# ST_LINK_V2-1.net
KiCad netlist of a schematic drawn in Altium Designer
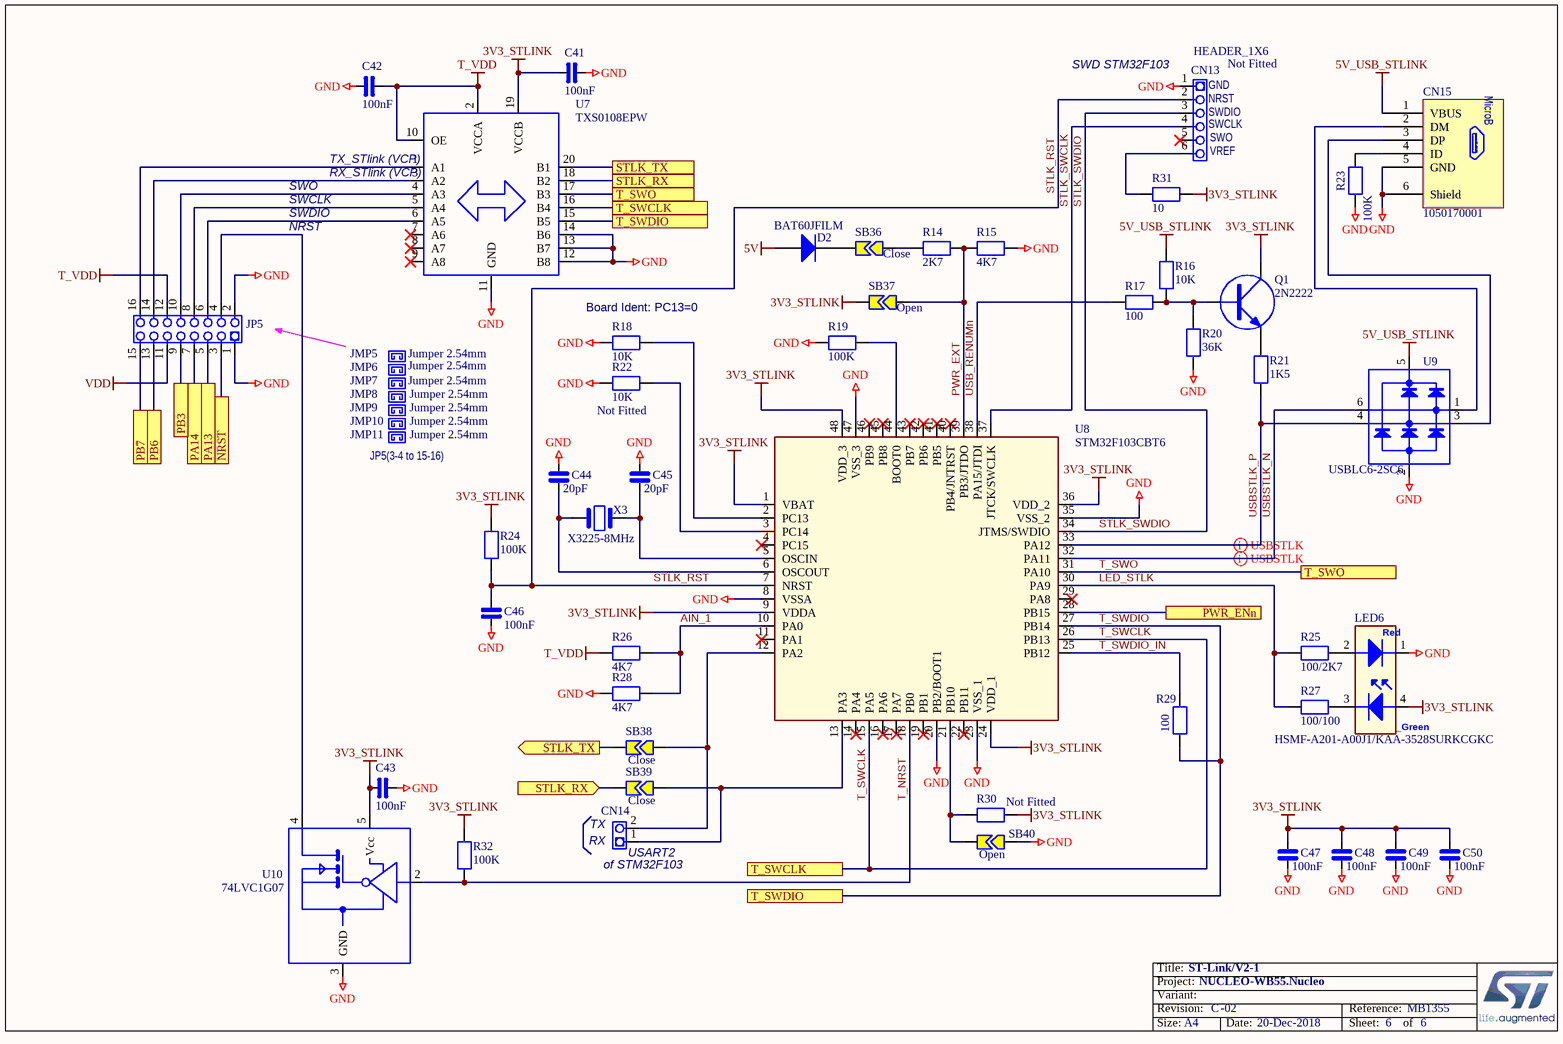
[diagram p0: ST_LINK_V2-1.SCHDOC]

(export (version "E")
  (design (tool "Eeschema 10.0.6"))
  (components
    (comp (ref "C41")
      (value "100nF")
      (footprint "0402_CAP_NPOL")
      (description "Capacitor_not polarized")
      (libsource (lib "ST_Lib3D") (part "CAP_NPOL"))
    )
    (comp (ref "C42")
      (value "100nF")
      (footprint "0402_CAP_NPOL")
      (description "Capacitor_not polarized")
      (libsource (lib "ST_Lib3D") (part "CAP_NPOL"))
    )
    (comp (ref "C43")
      (value "100nF")
      (footprint "0402_CAP_NPOL")
      (description "Capacitor_not polarized")
      (libsource (lib "ST_Lib3D") (part "CAP_NPOL"))
    )
    (comp (ref "C44")
      (value "20pF")
      (footprint "0402_CAP_NPOL")
      (description "Capacitor_not polarized")
      (libsource (lib "ST_Lib3D") (part "CAP_NPOL"))
    )
    (comp (ref "C45")
      (value "20pF")
      (footprint "0402_CAP_NPOL")
      (description "Capacitor_not polarized")
      (libsource (lib "ST_Lib3D") (part "CAP_NPOL"))
    )
    (comp (ref "C46")
      (value "100nF")
      (footprint "0402_CAP_NPOL")
      (description "Capacitor_not polarized")
      (libsource (lib "ST_Lib3D") (part "CAP_NPOL"))
    )
    (comp (ref "C47")
      (value "100nF")
      (footprint "0402_CAP_NPOL")
      (description "Capacitor_not polarized")
      (libsource (lib "ST_Lib3D") (part "CAP_NPOL"))
    )
    (comp (ref "C48")
      (value "100nF")
      (footprint "0402_CAP_NPOL")
      (description "Capacitor_not polarized")
      (libsource (lib "ST_Lib3D") (part "CAP_NPOL"))
    )
    (comp (ref "C49")
      (value "100nF")
      (footprint "0402_CAP_NPOL")
      (description "Capacitor_not polarized")
      (libsource (lib "ST_Lib3D") (part "CAP_NPOL"))
    )
    (comp (ref "C50")
      (value "100nF")
      (footprint "0402_CAP_NPOL")
      (description "Capacitor_not polarized")
      (libsource (lib "ST_Lib3D") (part "CAP_NPOL"))
    )
    (comp (ref "CN13")
      (value "HEADER_1X6")
      (footprint "Header NF 1x6x2.54 TH")
      (fields (field (name "FITTED") "Not Fitted"))
      (libsource (lib "Connector") (part "HEADER_1X6"))
    )
    (comp (ref "CN14")
      (value "HEADER_1X2")
      (footprint "Header NF 1x2x2.54 TH")
      (libsource (lib "Connector") (part "HEADER_1X2"))
    )
    (comp (ref "CN15")
      (value "1050170001")
      (footprint "USBMICROB_MOLEX_105017-0001_H2P90")
      (description "USB-MICRO-B, 1050170001, SMT, MOLEX")
      (libsource (lib "Connector") (part "1050170001"))
    )
    (comp (ref "D2")
      (value "BAT60JFILM")
      (footprint "SOD-323")
      (description "Default Diode")
      (fields (field (name "PUBLISHER") "Altium Limited"))
      (libsource (lib "MB1144_1") (part "Diode"))
    )
    (comp (ref "JMP5")
      (value "Jumper 2.54mm")
      (footprint "Jumper 2.54mm BLACK")
      (libsource (lib "Connector") (part "Jumper 2.54mm"))
    )
    (comp (ref "JMP6")
      (value "Jumper 2.54mm")
      (footprint "Jumper 2.54mm BLACK")
      (libsource (lib "Connector") (part "Jumper 2.54mm"))
    )
    (comp (ref "JMP7")
      (value "Jumper 2.54mm")
      (footprint "Jumper 2.54mm BLACK")
      (libsource (lib "Connector") (part "Jumper 2.54mm"))
    )
    (comp (ref "JMP8")
      (value "Jumper 2.54mm")
      (footprint "Jumper 2.54mm BLACK")
      (libsource (lib "Connector") (part "Jumper 2.54mm"))
    )
    (comp (ref "JMP9")
      (value "Jumper 2.54mm")
      (footprint "Jumper 2.54mm BLACK")
      (libsource (lib "Connector") (part "Jumper 2.54mm"))
    )
    (comp (ref "JMP10")
      (value "Jumper 2.54mm")
      (footprint "Jumper 2.54mm BLACK")
      (libsource (lib "Connector") (part "Jumper 2.54mm"))
    )
    (comp (ref "JMP11")
      (value "Jumper 2.54mm")
      (footprint "Jumper 2.54mm BLACK")
      (libsource (lib "Connector") (part "Jumper 2.54mm"))
    )
    (comp (ref "JP5")
      (value "HEADER_2X8")
      (footprint "Header M 2x8x2.54 TH V")
      (libsource (lib "Connector") (part "HEADER_2X8"))
    )
    (comp (ref "LED6")
      (value "HSMF-A201-A00J1/KAA-3528SURKCGKC")
      (footprint "HSMF-A201")
      (description "Bicolor Led")
      (libsource (lib "MB1136") (part "LD_BICOLOR_CMS"))
    )
    (comp (ref "Q1")
      (value "2N2222")
      (footprint "SOT23-3")
      (description "2N2222_SOT23")
      (libsource (lib "Active") (part "2N2222"))
    )
    (comp (ref "R14")
      (value "2K7")
      (footprint "0402_RES")
      (description "Resistor")
      (libsource (lib "Lib3D_Altium10_Schlib") (part "RES"))
    )
    (comp (ref "R15")
      (value "4K7")
      (footprint "0402_RES")
      (description "Resistor")
      (libsource (lib "Lib3D_Altium10_Schlib") (part "RES"))
    )
    (comp (ref "R16")
      (value "10K")
      (footprint "0402_RES")
      (description "Resistor")
      (libsource (lib "Lib3D_Altium10_Schlib") (part "RES"))
    )
    (comp (ref "R17")
      (value "100")
      (footprint "0402_RES")
      (description "Resistor")
      (libsource (lib "Lib3D_Altium10_Schlib") (part "RES"))
    )
    (comp (ref "R18")
      (value "10K")
      (footprint "0402_RES")
      (description "Resistor")
      (libsource (lib "Lib3D_Altium10_Schlib") (part "RES"))
    )
    (comp (ref "R19")
      (value "100K")
      (footprint "0402_RES")
      (description "Resistor")
      (libsource (lib "Lib3D_Altium10_Schlib") (part "RES"))
    )
    (comp (ref "R20")
      (value "36K")
      (footprint "0402_RES")
      (description "Resistor")
      (libsource (lib "Lib3D_Altium10_Schlib") (part "RES"))
    )
    (comp (ref "R21")
      (value "1K5")
      (footprint "0402_RES")
      (description "Resistor")
      (libsource (lib "Lib3D_Altium10_Schlib") (part "RES"))
    )
    (comp (ref "R22")
      (value "10K")
      (footprint "0402_RES")
      (description "Resistor")
      (fields (field (name "FITTED") "Not Fitted"))
      (libsource (lib "Lib3D_Altium10_Schlib") (part "RES"))
    )
    (comp (ref "R23")
      (value "100K")
      (footprint "0402_RES")
      (description "Resistor")
      (libsource (lib "Lib3D_Altium10_Schlib") (part "RES"))
    )
    (comp (ref "R24")
      (value "100K")
      (footprint "0402_RES")
      (description "Resistor")
      (libsource (lib "Lib3D_Altium10_Schlib") (part "RES"))
    )
    (comp (ref "R25")
      (value "100/2K7")
      (footprint "0402_RES")
      (description "Resistor")
      (libsource (lib "Lib3D_Altium10_Schlib") (part "RES"))
    )
    (comp (ref "R26")
      (value "4K7")
      (footprint "0402_RES")
      (description "Resistor")
      (libsource (lib "Lib3D_Altium10_Schlib") (part "RES"))
    )
    (comp (ref "R27")
      (value "100/100")
      (footprint "0402_RES")
      (description "Resistor")
      (libsource (lib "Lib3D_Altium10_Schlib") (part "RES"))
    )
    (comp (ref "R28")
      (value "4K7")
      (footprint "0402_RES")
      (description "Resistor")
      (libsource (lib "Lib3D_Altium10_Schlib") (part "RES"))
    )
    (comp (ref "R29")
      (value "100")
      (footprint "0402_RES")
      (description "Resistor")
      (libsource (lib "Lib3D_Altium10_Schlib") (part "RES"))
    )
    (comp (ref "R30")
      (value "~")
      (footprint "0402_RES")
      (description "Resistor")
      (fields (field (name "FITTED") "Not Fitted"))
      (libsource (lib "Lib3D_Altium10_Schlib") (part "RES"))
    )
    (comp (ref "R31")
      (value "10")
      (footprint "0402_RES")
      (description "Resistor")
      (libsource (lib "Lib3D_Altium10_Schlib") (part "RES"))
    )
    (comp (ref "R32")
      (value "100K")
      (footprint "0402_RES")
      (description "Resistor")
      (libsource (lib "Lib3D_Altium10_Schlib") (part "RES"))
    )
    (comp (ref "SB36")
      (value "Close")
      (footprint "SB-tiny")
      (description "Solder Jumper")
      (fields (field (name "PUBLISHER") "Altium Limited"))
      (libsource (lib "Lib3D_Altium10_Schlib") (part "Strap2"))
    )
    (comp (ref "SB37")
      (value "Open")
      (footprint "SB-tiny")
      (description "Solder Jumper")
      (fields (field (name "PUBLISHER") "Altium Limited"))
      (libsource (lib "Lib3D_Altium10_Schlib") (part "Strap2"))
    )
    (comp (ref "SB38")
      (value "Close")
      (footprint "SB-tiny")
      (description "Solder Jumper")
      (fields (field (name "PUBLISHER") "Altium Limited"))
      (libsource (lib "Lib3D_Altium10_Schlib") (part "Strap2"))
    )
    (comp (ref "SB39")
      (value "Close")
      (footprint "SB-tiny")
      (description "Solder Jumper")
      (fields (field (name "PUBLISHER") "Altium Limited"))
      (libsource (lib "Lib3D_Altium10_Schlib") (part "Strap2"))
    )
    (comp (ref "SB40")
      (value "Open")
      (footprint "SB-tiny")
      (description "Solder Jumper")
      (fields (field (name "PUBLISHER") "Altium Limited"))
      (libsource (lib "Lib3D_Altium10_Schlib") (part "Strap2"))
    )
    (comp (ref "U7")
      (value "TXS0108EPW")
      (footprint "TSSOP20")
      (description "TXS0108E Bi-directional Level Shifter TSSOP20")
      (libsource (lib "Active") (part "TXS0108EPW"))
    )
    (comp (ref "U8")
      (value "STM32F103CBT6")
      (footprint "LQFP48_7X7_P050")
      (description "Medium-density performance line ARM-based 32-bit MCU with 128KB Flash")
      (libsource (lib "Active") (part "STM32F103CBT6"))
    )
    (comp (ref "U9") (value "USBLC6-2SC6") (footprint "SOT23-6") (libsource (lib "Active") (part "USBLC6-2")))
    (comp (ref "U10")
      (value "74LVC1G07")
      (footprint "SOT353-1")
      (libsource (lib "ST_Lib3D") (part "74LVC1G07"))
    )
    (comp (ref "X3")
      (value "X3225-8MHz")
      (footprint "X3225")
      (description "Crystal 8MHz")
      (libsource (lib "Xtal") (part "X3225"))
    )
  )
  (nets
    (net (code "1") (name "/AIN_1") (class "Default")
      (node (ref "R26") (pin "1") (pinfunction "1_1") (pintype "passive"))
      (node (ref "R28") (pin "1") (pinfunction "1_1") (pintype "passive"))
      (node (ref "U8") (pin "10") (pinfunction "PA0_10") (pintype "passive"))
    )
    (net (code "2") (name "/LED_STLK") (class "Default")
      (node (ref "R25") (pin "2") (pinfunction "2_2") (pintype "passive"))
      (node (ref "R27") (pin "2") (pinfunction "2_2") (pintype "passive"))
      (node (ref "U8") (pin "30") (pinfunction "PA9_30") (pintype "passive"))
    )
    (net (code "3") (name "/NRST") (class "Default")
      (node (ref "JP5") (pin "3") (pinfunction "3_3") (pintype "passive"))
    )
    (net (code "4") (name "/PA13") (class "Default")
      (node (ref "JP5") (pin "5") (pinfunction "5_5") (pintype "passive"))
    )
    (net (code "5") (name "/PA14") (class "Default")
      (node (ref "JP5") (pin "7") (pinfunction "7_7") (pintype "passive"))
    )
    (net (code "6") (name "/PB3") (class "Default")
      (node (ref "JP5") (pin "9") (pinfunction "9_9") (pintype "passive"))
    )
    (net (code "7") (name "/PB6") (class "Default")
      (node (ref "JP5") (pin "13") (pinfunction "13_13") (pintype "passive"))
    )
    (net (code "8") (name "/PB7") (class "Default")
      (node (ref "JP5") (pin "15") (pinfunction "15_15") (pintype "passive"))
    )
    (net (code "9") (name "/PWR_ENn") (class "Default")
      (node (ref "U8") (pin "28") (pinfunction "PB15_28") (pintype "passive"))
    )
    (net (code "10") (name "/PWR_EXT") (class "Default")
      (node (ref "R14") (pin "2") (pinfunction "2_2") (pintype "passive"))
      (node (ref "R15") (pin "1") (pinfunction "1_1") (pintype "passive"))
      (node (ref "SB37") (pin "2") (pinfunction "2_2") (pintype "passive"))
      (node (ref "U8") (pin "39") (pinfunction "PB3/JTDO_39") (pintype "passive"))
    )
    (net (code "11") (name "/STLK_RST") (class "Default")
      (node (ref "C46") (pin "2") (pinfunction "2_2") (pintype "passive"))
      (node (ref "CN13") (pin "2") (pinfunction "2_2") (pintype "passive"))
      (node (ref "R24") (pin "1") (pinfunction "1_1") (pintype "passive"))
      (node (ref "U8") (pin "7") (pinfunction "NRST_7") (pintype "passive"))
    )
    (net (code "12") (name "/STLK_RX") (class "Default")
      (node (ref "SB39") (pin "1") (pinfunction "1_1") (pintype "passive"))
      (node (ref "U7") (pin "18") (pinfunction "B2_18") (pintype "passive"))
    )
    (net (code "13") (name "/STLK_SWCLK") (class "Default")
      (node (ref "CN13") (pin "4") (pinfunction "4_4") (pintype "passive"))
      (node (ref "U8") (pin "37") (pinfunction "JTCK/SWCLK_37") (pintype "passive"))
    )
    (net (code "14") (name "/STLK_SWDIO") (class "Default")
      (node (ref "CN13") (pin "3") (pinfunction "3_3") (pintype "passive"))
      (node (ref "U8") (pin "34") (pinfunction "JTMS/SWDIO_34") (pintype "passive"))
    )
    (net (code "15") (name "/STLK_TX") (class "Default")
      (node (ref "SB38") (pin "1") (pinfunction "1_1") (pintype "passive"))
      (node (ref "U7") (pin "20") (pinfunction "B1_20") (pintype "passive"))
    )
    (net (code "16") (name "/T_NRST") (class "Default")
      (node (ref "R32") (pin "1") (pinfunction "1_1") (pintype "passive"))
      (node (ref "U10") (pin "2") (pinfunction "A_2") (pintype "passive"))
      (node (ref "U8") (pin "18") (pinfunction "PB0_18") (pintype "passive"))
    )
    (net (code "17") (name "/T_SWCLK") (class "Default")
      (node (ref "U7") (pin "16") (pinfunction "B4_16") (pintype "passive"))
      (node (ref "U8") (pin "15") (pinfunction "PA5_15") (pintype "passive"))
      (node (ref "U8") (pin "26") (pinfunction "PB13_26") (pintype "passive"))
    )
    (net (code "18") (name "/T_SWDIO") (class "Default")
      (node (ref "R29") (pin "1") (pinfunction "1_1") (pintype "passive"))
      (node (ref "U7") (pin "15") (pinfunction "B5_15") (pintype "passive"))
      (node (ref "U8") (pin "27") (pinfunction "PB14_27") (pintype "passive"))
    )
    (net (code "19") (name "/T_SWDIO_IN") (class "Default")
      (node (ref "R29") (pin "2") (pinfunction "2_2") (pintype "passive"))
      (node (ref "U8") (pin "25") (pinfunction "PB12_25") (pintype "passive"))
    )
    (net (code "20") (name "/T_SWO") (class "Default")
      (node (ref "U7") (pin "17") (pinfunction "B3_17") (pintype "passive"))
      (node (ref "U8") (pin "31") (pinfunction "PA10_31") (pintype "passive"))
    )
    (net (code "21") (name "/USBSTLK_N") (class "Default")
      (node (ref "U8") (pin "32") (pinfunction "PA11_32") (pintype "passive"))
      (node (ref "U9") (pin "6") (pinfunction "6_6") (pintype "passive"))
    )
    (net (code "22") (name "/USBSTLK_P") (class "Default")
      (node (ref "R21") (pin "1") (pinfunction "1_1") (pintype "passive"))
      (node (ref "U8") (pin "33") (pinfunction "PA12_33") (pintype "passive"))
      (node (ref "U9") (pin "4") (pinfunction "4_4") (pintype "passive"))
    )
    (net (code "23") (name "/USB_RENUMn") (class "Default")
      (node (ref "R17") (pin "2") (pinfunction "2_2") (pintype "passive"))
      (node (ref "U8") (pin "38") (pinfunction "PA15/JTDI_38") (pintype "passive"))
    )
    (net (code "24") (name "3V3_STLINK") (class "Default")
      (node (ref "C41") (pin "1") (pinfunction "1_1") (pintype "passive"))
      (node (ref "C43") (pin "1") (pinfunction "1_1") (pintype "passive"))
      (node (ref "C47") (pin "1") (pinfunction "1_1") (pintype "passive"))
      (node (ref "C48") (pin "1") (pinfunction "1_1") (pintype "passive"))
      (node (ref "C49") (pin "1") (pinfunction "1_1") (pintype "passive"))
      (node (ref "C50") (pin "1") (pinfunction "1_1") (pintype "passive"))
      (node (ref "LED6") (pin "4") (pinfunction "4_4") (pintype "passive"))
      (node (ref "Q1") (pin "3") (pinfunction "C_3") (pintype "passive"))
      (node (ref "R24") (pin "2") (pinfunction "2_2") (pintype "passive"))
      (node (ref "R30") (pin "1") (pinfunction "1_1") (pintype "passive"))
      (node (ref "R31") (pin "2") (pinfunction "2_2") (pintype "passive"))
      (node (ref "R32") (pin "2") (pinfunction "2_2") (pintype "passive"))
      (node (ref "SB37") (pin "1") (pinfunction "1_1") (pintype "passive"))
      (node (ref "U10") (pin "5") (pinfunction "Vcc_5") (pintype "passive"))
      (node (ref "U7") (pin "19") (pinfunction "VCCB_19") (pintype "passive"))
      (node (ref "U8") (pin "1") (pinfunction "VBAT_1") (pintype "passive"))
      (node (ref "U8") (pin "24") (pinfunction "VDD_1_24") (pintype "passive"))
      (node (ref "U8") (pin "36") (pinfunction "VDD_2_36") (pintype "passive"))
      (node (ref "U8") (pin "48") (pinfunction "VDD_3_48") (pintype "passive"))
      (node (ref "U8") (pin "9") (pinfunction "VDDA_9") (pintype "passive"))
    )
    (net (code "25") (name "5V") (class "Default")
      (node (ref "D2") (pin "1") (pinfunction "A_1") (pintype "passive"))
    )
    (net (code "26") (name "5V_USB_STLINK") (class "Default")
      (node (ref "CN15") (pin "1") (pinfunction "VBUS_1") (pintype "passive"))
      (node (ref "R16") (pin "2") (pinfunction "2_2") (pintype "passive"))
      (node (ref "U9") (pin "5") (pinfunction "5_5") (pintype "passive"))
    )
    (net (code "27") (name "GND") (class "Default")
      (node (ref "C41") (pin "2") (pinfunction "2_2") (pintype "passive"))
      (node (ref "C42") (pin "1") (pinfunction "1_1") (pintype "passive"))
      (node (ref "C43") (pin "2") (pinfunction "2_2") (pintype "passive"))
      (node (ref "C44") (pin "1") (pinfunction "1_1") (pintype "passive"))
      (node (ref "C45") (pin "1") (pinfunction "1_1") (pintype "passive"))
      (node (ref "C46") (pin "1") (pinfunction "1_1") (pintype "passive"))
      (node (ref "C47") (pin "2") (pinfunction "2_2") (pintype "passive"))
      (node (ref "C48") (pin "2") (pinfunction "2_2") (pintype "passive"))
      (node (ref "C49") (pin "2") (pinfunction "2_2") (pintype "passive"))
      (node (ref "C50") (pin "2") (pinfunction "2_2") (pintype "passive"))
      (node (ref "CN13") (pin "1") (pinfunction "1_1") (pintype "passive"))
      (node (ref "CN15") (pin "5") (pinfunction "GND_5") (pintype "passive"))
      (node (ref "CN15") (pin "6") (pinfunction "Shield_6") (pintype "passive"))
      (node (ref "JP5") (pin "1") (pinfunction "1_1") (pintype "passive"))
      (node (ref "JP5") (pin "2") (pinfunction "2_2") (pintype "passive"))
      (node (ref "LED6") (pin "1") (pinfunction "1_1") (pintype "passive"))
      (node (ref "R15") (pin "2") (pinfunction "2_2") (pintype "passive"))
      (node (ref "R18") (pin "2") (pinfunction "2_2") (pintype "passive"))
      (node (ref "R19") (pin "1") (pinfunction "1_1") (pintype "passive"))
      (node (ref "R20") (pin "1") (pinfunction "1_1") (pintype "passive"))
      (node (ref "R22") (pin "2") (pinfunction "2_2") (pintype "passive"))
      (node (ref "R23") (pin "1") (pinfunction "1_1") (pintype "passive"))
      (node (ref "R28") (pin "2") (pinfunction "2_2") (pintype "passive"))
      (node (ref "SB40") (pin "2") (pinfunction "2_2") (pintype "passive"))
      (node (ref "U10") (pin "3") (pinfunction "GND_3") (pintype "passive"))
      (node (ref "U7") (pin "11") (pinfunction "GND_11") (pintype "passive"))
      (node (ref "U7") (pin "12") (pinfunction "B8_12") (pintype "passive"))
      (node (ref "U7") (pin "13") (pinfunction "B7_13") (pintype "passive"))
      (node (ref "U7") (pin "14") (pinfunction "B6_14") (pintype "passive"))
      (node (ref "U8") (pin "20") (pinfunction "PB2/BOOT1_20") (pintype "passive"))
      (node (ref "U8") (pin "23") (pinfunction "VSS_1_23") (pintype "passive"))
      (node (ref "U8") (pin "35") (pinfunction "VSS_2_35") (pintype "passive"))
      (node (ref "U8") (pin "47") (pinfunction "VSS_3_47") (pintype "passive"))
      (node (ref "U8") (pin "8") (pinfunction "VSSA_8") (pintype "passive"))
      (node (ref "U9") (pin "2") (pinfunction "2_2") (pintype "passive"))
    )
    (net (code "28") (name "Net-(CN13-Pad6)") (class "Default")
      (node (ref "CN13") (pin "6") (pinfunction "6_6") (pintype "passive"))
      (node (ref "R31") (pin "1") (pinfunction "1_1") (pintype "passive"))
    )
    (net (code "29") (name "Net-(CN15-DM)") (class "Default")
      (node (ref "CN15") (pin "2") (pinfunction "DM_2") (pintype "passive"))
      (node (ref "U9") (pin "1") (pinfunction "1_1") (pintype "passive"))
    )
    (net (code "30") (name "Net-(CN15-DP)") (class "Default")
      (node (ref "CN15") (pin "3") (pinfunction "DP_3") (pintype "passive"))
      (node (ref "U9") (pin "3") (pinfunction "3_3") (pintype "passive"))
    )
    (net (code "31") (name "Net-(CN15-ID)") (class "Default")
      (node (ref "CN15") (pin "4") (pinfunction "ID_4") (pintype "passive"))
      (node (ref "R23") (pin "2") (pinfunction "2_2") (pintype "passive"))
    )
    (net (code "32") (name "Net-(D2-K)") (class "Default")
      (node (ref "D2") (pin "2") (pinfunction "K_2") (pintype "passive"))
      (node (ref "SB36") (pin "1") (pinfunction "1_1") (pintype "passive"))
    )
    (net (code "33") (name "Net-(LED6-Pad2)") (class "Default")
      (node (ref "LED6") (pin "2") (pinfunction "2_2") (pintype "passive"))
      (node (ref "R25") (pin "1") (pinfunction "1_1") (pintype "passive"))
    )
    (net (code "34") (name "Net-(LED6-Pad3)") (class "Default")
      (node (ref "LED6") (pin "3") (pinfunction "3_3") (pintype "passive"))
      (node (ref "R27") (pin "1") (pinfunction "1_1") (pintype "passive"))
    )
    (net (code "35") (name "Net-(Q1-B)") (class "Default")
      (node (ref "Q1") (pin "1") (pinfunction "B_1") (pintype "passive"))
      (node (ref "R16") (pin "1") (pinfunction "1_1") (pintype "passive"))
      (node (ref "R17") (pin "1") (pinfunction "1_1") (pintype "passive"))
      (node (ref "R20") (pin "2") (pinfunction "2_2") (pintype "passive"))
    )
    (net (code "36") (name "Net-(Q1-E)") (class "Default")
      (node (ref "Q1") (pin "2") (pinfunction "E_2") (pintype "passive"))
      (node (ref "R21") (pin "2") (pinfunction "2_2") (pintype "passive"))
    )
    (net (code "37") (name "Net-(R14-Pad1)") (class "Default")
      (node (ref "R14") (pin "1") (pinfunction "1_1") (pintype "passive"))
      (node (ref "SB36") (pin "2") (pinfunction "2_2") (pintype "passive"))
    )
    (net (code "38") (name "Net-(U7-A1)") (class "Default")
      (node (ref "JP5") (pin "16") (pinfunction "16_16") (pintype "passive"))
      (node (ref "U7") (pin "1") (pinfunction "A1_1") (pintype "passive"))
    )
    (net (code "39") (name "Net-(U7-A2)") (class "Default")
      (node (ref "JP5") (pin "14") (pinfunction "14_14") (pintype "passive"))
      (node (ref "U7") (pin "3") (pinfunction "A2_3") (pintype "passive"))
    )
    (net (code "40") (name "Net-(U7-A3)") (class "Default")
      (node (ref "JP5") (pin "10") (pinfunction "10_10") (pintype "passive"))
      (node (ref "U7") (pin "4") (pinfunction "A3_4") (pintype "passive"))
    )
    (net (code "41") (name "Net-(U7-A4)") (class "Default")
      (node (ref "JP5") (pin "8") (pinfunction "8_8") (pintype "passive"))
      (node (ref "U7") (pin "5") (pinfunction "A4_5") (pintype "passive"))
    )
    (net (code "42") (name "Net-(U7-A5)") (class "Default")
      (node (ref "JP5") (pin "6") (pinfunction "6_6") (pintype "passive"))
      (node (ref "U7") (pin "6") (pinfunction "A5_6") (pintype "passive"))
    )
    (net (code "43") (name "Net-(U8-BOOT0)") (class "Default")
      (node (ref "R19") (pin "2") (pinfunction "2_2") (pintype "passive"))
      (node (ref "U8") (pin "44") (pinfunction "BOOT0_44") (pintype "passive"))
    )
    (net (code "44") (name "Net-(U8-OSCIN)") (class "Default")
      (node (ref "C45") (pin "2") (pinfunction "2_2") (pintype "passive"))
      (node (ref "U8") (pin "5") (pinfunction "OSCIN_5") (pintype "passive"))
      (node (ref "X3") (pin "3") (pinfunction "3_3") (pintype "passive"))
    )
    (net (code "45") (name "Net-(U8-OSCOUT)") (class "Default")
      (node (ref "C44") (pin "2") (pinfunction "2_2") (pintype "passive"))
      (node (ref "U8") (pin "6") (pinfunction "OSCOUT_6") (pintype "passive"))
      (node (ref "X3") (pin "1") (pinfunction "1_1") (pintype "passive"))
    )
    (net (code "46") (name "Net-(U8-PA2)") (class "Default")
      (node (ref "CN14") (pin "2") (pinfunction "2_2") (pintype "passive"))
      (node (ref "SB38") (pin "2") (pinfunction "2_2") (pintype "passive"))
      (node (ref "U8") (pin "12") (pinfunction "PA2_12") (pintype "passive"))
    )
    (net (code "47") (name "Net-(U8-PA3)") (class "Default")
      (node (ref "CN14") (pin "1") (pinfunction "1_1") (pintype "passive"))
      (node (ref "SB39") (pin "2") (pinfunction "2_2") (pintype "passive"))
      (node (ref "U8") (pin "13") (pinfunction "PA3_13") (pintype "passive"))
    )
    (net (code "48") (name "Net-(U8-PB10)") (class "Default")
      (node (ref "R30") (pin "2") (pinfunction "2_2") (pintype "passive"))
      (node (ref "SB40") (pin "1") (pinfunction "1_1") (pintype "passive"))
      (node (ref "U8") (pin "21") (pinfunction "PB10_21") (pintype "passive"))
    )
    (net (code "49") (name "Net-(U8-PC13)") (class "Default")
      (node (ref "R18") (pin "1") (pinfunction "1_1") (pintype "passive"))
      (node (ref "U8") (pin "2") (pinfunction "PC13_2") (pintype "passive"))
    )
    (net (code "50") (name "Net-(U8-PC14)") (class "Default")
      (node (ref "R22") (pin "1") (pinfunction "1_1") (pintype "passive"))
      (node (ref "U8") (pin "3") (pinfunction "PC14_3") (pintype "passive"))
    )
    (net (code "51") (name "Net-(U10-Y)") (class "Default")
      (node (ref "JP5") (pin "4") (pinfunction "4_4") (pintype "passive"))
      (node (ref "U10") (pin "4") (pinfunction "Y_4") (pintype "passive"))
    )
    (net (code "52") (name "T_VDD") (class "Default")
      (node (ref "C42") (pin "2") (pinfunction "2_2") (pintype "passive"))
      (node (ref "JP5") (pin "12") (pinfunction "12_12") (pintype "passive"))
      (node (ref "R26") (pin "2") (pinfunction "2_2") (pintype "passive"))
      (node (ref "U7") (pin "10") (pinfunction "OE_10") (pintype "passive"))
      (node (ref "U7") (pin "2") (pinfunction "VCCA_2") (pintype "passive"))
    )
    (net (code "53") (name "VDD") (class "Default")
      (node (ref "JP5") (pin "11") (pinfunction "11_11") (pintype "passive"))
    )
    (net (code "54") (name "unconnected-(CN13-Pad5)") (class "Default")
      (node (ref "CN13") (pin "5") (pinfunction "5_5") (pintype "passive+no_connect"))
    )
    (net (code "55") (name "unconnected-(U7-A6-Pad7)") (class "Default")
      (node (ref "U7") (pin "7") (pinfunction "A6_7") (pintype "passive+no_connect"))
    )
    (net (code "56") (name "unconnected-(U7-A7-Pad8)") (class "Default")
      (node (ref "U7") (pin "8") (pinfunction "A7_8") (pintype "passive+no_connect"))
    )
    (net (code "57") (name "unconnected-(U7-A8-Pad9)") (class "Default")
      (node (ref "U7") (pin "9") (pinfunction "A8_9") (pintype "passive+no_connect"))
    )
    (net (code "58") (name "unconnected-(U8-PA1-Pad11)") (class "Default")
      (node (ref "U8") (pin "11") (pinfunction "PA1_11") (pintype "passive+no_connect"))
    )
    (net (code "59") (name "unconnected-(U8-PA4-Pad14)") (class "Default")
      (node (ref "U8") (pin "14") (pinfunction "PA4_14") (pintype "passive+no_connect"))
    )
    (net (code "60") (name "unconnected-(U8-PA6-Pad16)") (class "Default")
      (node (ref "U8") (pin "16") (pinfunction "PA6_16") (pintype "passive+no_connect"))
    )
    (net (code "61") (name "unconnected-(U8-PA7-Pad17)") (class "Default")
      (node (ref "U8") (pin "17") (pinfunction "PA7_17") (pintype "passive+no_connect"))
    )
    (net (code "62") (name "unconnected-(U8-PA8-Pad29)") (class "Default")
      (node (ref "U8") (pin "29") (pinfunction "PA8_29") (pintype "passive+no_connect"))
    )
    (net (code "63") (name "unconnected-(U8-PB1-Pad19)") (class "Default")
      (node (ref "U8") (pin "19") (pinfunction "PB1_19") (pintype "passive+no_connect"))
    )
    (net (code "64") (name "unconnected-(U8-PB4{slash}JNTRST-Pad40)") (class "Default")
      (node (ref "U8") (pin "40") (pinfunction "PB4/JNTRST_40") (pintype "passive+no_connect"))
    )
    (net (code "65") (name "unconnected-(U8-PB5-Pad41)") (class "Default")
      (node (ref "U8") (pin "41") (pinfunction "PB5_41") (pintype "passive+no_connect"))
    )
    (net (code "66") (name "unconnected-(U8-PB6-Pad42)") (class "Default")
      (node (ref "U8") (pin "42") (pinfunction "PB6_42") (pintype "passive+no_connect"))
    )
    (net (code "67") (name "unconnected-(U8-PB7-Pad43)") (class "Default")
      (node (ref "U8") (pin "43") (pinfunction "PB7_43") (pintype "passive+no_connect"))
    )
    (net (code "68") (name "unconnected-(U8-PB8-Pad45)") (class "Default")
      (node (ref "U8") (pin "45") (pinfunction "PB8_45") (pintype "passive+no_connect"))
    )
    (net (code "69") (name "unconnected-(U8-PB9-Pad46)") (class "Default")
      (node (ref "U8") (pin "46") (pinfunction "PB9_46") (pintype "passive+no_connect"))
    )
    (net (code "70") (name "unconnected-(U8-PB11-Pad22)") (class "Default")
      (node (ref "U8") (pin "22") (pinfunction "PB11_22") (pintype "passive+no_connect"))
    )
    (net (code "71") (name "unconnected-(U8-PC15-Pad4)") (class "Default")
      (node (ref "U8") (pin "4") (pinfunction "PC15_4") (pintype "passive+no_connect"))
    )
  )
)
